# uart_adm3222.net
KiCad netlist of a schematic drawn in Altium Designer
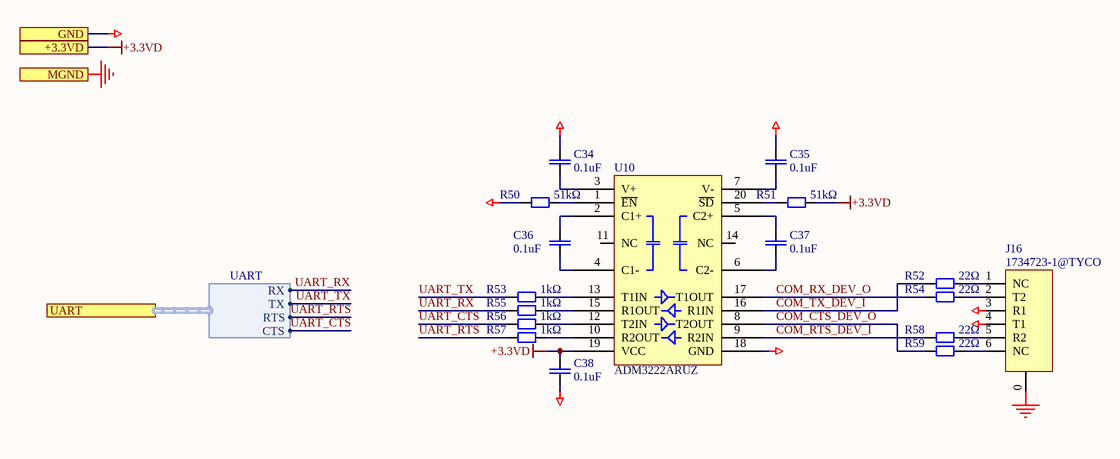
[diagram p0: uart_adm3222.SchDoc]

(export (version "E")
  (design (tool "Eeschema 10.0.6"))
  (components
    (comp (ref "C34")
      (value "0.1uF")
      (footprint "CAPC2012N")
      (description "Generic ceramic SMD capacitor")
      (fields (field (name "MAINTAINER") "Evgeniy Kotov"))
      (libsource (lib "[Capacitors] Capacitors SMD") (part "CAPC"))
    )
    (comp (ref "C35")
      (value "0.1uF")
      (footprint "CAPC2012N")
      (description "Generic ceramic SMD capacitor")
      (fields (field (name "MAINTAINER") "Evgeniy Kotov"))
      (libsource (lib "[Capacitors] Capacitors SMD") (part "CAPC"))
    )
    (comp (ref "C36")
      (value "0.1uF")
      (footprint "CAPC2012N")
      (description "Generic ceramic SMD capacitor")
      (fields (field (name "MAINTAINER") "Evgeniy Kotov"))
      (libsource (lib "[Capacitors] Capacitors SMD") (part "CAPC"))
    )
    (comp (ref "C37")
      (value "0.1uF")
      (footprint "CAPC2012N")
      (description "Generic ceramic SMD capacitor")
      (fields (field (name "MAINTAINER") "Evgeniy Kotov"))
      (libsource (lib "[Capacitors] Capacitors SMD") (part "CAPC"))
    )
    (comp (ref "C38")
      (value "0.1uF")
      (footprint "CAPC2012N")
      (description "Generic ceramic SMD capacitor")
      (fields (field (name "MAINTAINER") "Evgeniy Kotov"))
      (libsource (lib "[Capacitors] Capacitors SMD") (part "CAPC"))
    )
    (comp (ref "J16")
      (value "1734723-1@TYCO")
      (footprint "RJ14")
      (libsource (lib "[Connectors] Miscellaneous") (part "RJ-14"))
    )
    (comp (ref "R50")
      (value "51kΩ")
      (footprint "RESC2012N")
      (description "Resistor, Generic, SMD")
      (fields (field (name "MAINTAINER") "Evgeniy Kotov"))
      (libsource (lib "[Resistors] Resistors SMD") (part "RESC"))
    )
    (comp (ref "R51")
      (value "51kΩ")
      (footprint "RESC2012N")
      (description "Resistor, Generic, SMD")
      (fields (field (name "MAINTAINER") "Evgeniy Kotov"))
      (libsource (lib "[Resistors] Resistors SMD") (part "RESC"))
    )
    (comp (ref "R52")
      (value "22Ω")
      (footprint "RESC1608N")
      (description "Resistor, Generic, SMD")
      (fields (field (name "MAINTAINER") "Evgeniy Kotov"))
      (libsource (lib "[Resistors] Resistors SMD") (part "RESC"))
    )
    (comp (ref "R53")
      (value "1kΩ")
      (footprint "RESC2012N")
      (description "Resistor, Generic, SMD")
      (fields (field (name "MAINTAINER") "Evgeniy Kotov"))
      (libsource (lib "[Resistors] Resistors SMD") (part "RESC"))
    )
    (comp (ref "R54")
      (value "22Ω")
      (footprint "RESC1608N")
      (description "Resistor, Generic, SMD")
      (fields (field (name "MAINTAINER") "Evgeniy Kotov"))
      (libsource (lib "[Resistors] Resistors SMD") (part "RESC"))
    )
    (comp (ref "R55")
      (value "1kΩ")
      (footprint "RESC2012N")
      (description "Resistor, Generic, SMD")
      (fields (field (name "MAINTAINER") "Evgeniy Kotov"))
      (libsource (lib "[Resistors] Resistors SMD") (part "RESC"))
    )
    (comp (ref "R56")
      (value "1kΩ")
      (footprint "RESC2012N")
      (description "Resistor, Generic, SMD")
      (fields (field (name "MAINTAINER") "Evgeniy Kotov"))
      (libsource (lib "[Resistors] Resistors SMD") (part "RESC"))
    )
    (comp (ref "R57")
      (value "1kΩ")
      (footprint "RESC2012N")
      (description "Resistor, Generic, SMD")
      (fields (field (name "MAINTAINER") "Evgeniy Kotov"))
      (libsource (lib "[Resistors] Resistors SMD") (part "RESC"))
    )
    (comp (ref "R58")
      (value "22Ω")
      (footprint "RESC1608N")
      (description "Resistor, Generic, SMD")
      (fields (field (name "MAINTAINER") "Evgeniy Kotov"))
      (libsource (lib "[Resistors] Resistors SMD") (part "RESC"))
    )
    (comp (ref "R59")
      (value "22Ω")
      (footprint "RESC1608N")
      (description "Resistor, Generic, SMD")
      (fields (field (name "MAINTAINER") "Evgeniy Kotov"))
      (libsource (lib "[Resistors] Resistors SMD") (part "RESC"))
    )
    (comp (ref "U10")
      (value "ADM3222ARUZ")
      (footprint "SOP65P640X110-20N")
      (description "RS232")
      (libsource (lib "[ICs And Semiconductors] Analog & Interface") (part "ADM3222ARU"))
    )
  )
  (nets
    (net (code "2") (name "+3.3VD") (class "Default")
      (node (ref "C38") (pin "2") (pintype "passive"))
      (node (ref "R51") (pin "2") (pintype "passive"))
      (node (ref "U10") (pin "19") (pinfunction "VCC_19") (pintype "passive"))
    )
    (net (code "3") (name "/COM_CTS_DEV_O") (class "Default")
      (node (ref "R59") (pin "1") (pintype "passive"))
      (node (ref "U10") (pin "8") (pinfunction "T2OUT_8") (pintype "passive"))
    )
    (net (code "4") (name "/COM_RTS_DEV_I") (class "Default")
      (node (ref "R58") (pin "1") (pintype "passive"))
      (node (ref "U10") (pin "9") (pinfunction "R2IN_9") (pintype "passive"))
    )
    (net (code "5") (name "/COM_RX_DEV_O") (class "Default")
      (node (ref "R54") (pin "1") (pintype "passive"))
      (node (ref "U10") (pin "17") (pinfunction "T1OUT_17") (pintype "passive"))
    )
    (net (code "6") (name "/COM_TX_DEV_I") (class "Default")
      (node (ref "R52") (pin "1") (pintype "passive"))
      (node (ref "U10") (pin "16") (pinfunction "R1IN_16") (pintype "passive"))
    )
    (net (code "7") (name "/UART_CTS") (class "Default") (node (ref "R56") (pin "1") (pintype "passive")))
    (net (code "8") (name "/UART_RTS") (class "Default") (node (ref "R57") (pin "1") (pintype "passive")))
    (net (code "9") (name "/UART_RX") (class "Default") (node (ref "R55") (pin "1") (pintype "passive")))
    (net (code "10") (name "/UART_TX") (class "Default") (node (ref "R53") (pin "1") (pintype "passive")))
    (net (code "12") (name "GND") (class "Default")
      (node (ref "C34") (pin "2") (pintype "passive"))
      (node (ref "C35") (pin "2") (pintype "passive"))
      (node (ref "C38") (pin "1") (pintype "passive"))
      (node (ref "J16") (pin "3") (pinfunction "R1_3") (pintype "passive"))
      (node (ref "J16") (pin "4") (pinfunction "T1_4") (pintype "passive"))
      (node (ref "R50") (pin "1") (pintype "passive"))
      (node (ref "U10") (pin "18") (pinfunction "GND_18") (pintype "passive"))
    )
    (net (code "13") (name "MGND") (class "Default") (node (ref "J16") (pin "0") (pintype "passive")))
    (net (code "14") (name "Net-(J16-NC-Pad1)") (class "Default")
      (node (ref "J16") (pin "1") (pinfunction "NC_1") (pintype "passive"))
      (node (ref "R52") (pin "2") (pintype "passive"))
    )
    (net (code "15") (name "Net-(J16-NC-Pad6)") (class "Default")
      (node (ref "J16") (pin "6") (pinfunction "NC_6") (pintype "passive"))
      (node (ref "R59") (pin "2") (pintype "passive"))
    )
    (net (code "16") (name "Net-(J16-R2)") (class "Default")
      (node (ref "J16") (pin "5") (pinfunction "R2_5") (pintype "passive"))
      (node (ref "R58") (pin "2") (pintype "passive"))
    )
    (net (code "17") (name "Net-(J16-T2)") (class "Default")
      (node (ref "J16") (pin "2") (pinfunction "T2_2") (pintype "passive"))
      (node (ref "R54") (pin "2") (pintype "passive"))
    )
    (net (code "18") (name "Net-(U10-C1+)") (class "Default")
      (node (ref "C36") (pin "2") (pintype "passive"))
      (node (ref "U10") (pin "2") (pinfunction "C1+_2") (pintype "passive"))
    )
    (net (code "19") (name "Net-(U10-C1-)") (class "Default")
      (node (ref "C36") (pin "1") (pintype "passive"))
      (node (ref "U10") (pin "4") (pinfunction "C1-_4") (pintype "passive"))
    )
    (net (code "20") (name "Net-(U10-C2+)") (class "Default")
      (node (ref "C37") (pin "2") (pintype "passive"))
      (node (ref "U10") (pin "5") (pinfunction "C2+_5") (pintype "passive"))
    )
    (net (code "21") (name "Net-(U10-C2-)") (class "Default")
      (node (ref "C37") (pin "1") (pintype "passive"))
      (node (ref "U10") (pin "6") (pinfunction "C2-_6") (pintype "passive"))
    )
    (net (code "22") (name "Net-(U10-R1OUT)") (class "Default")
      (node (ref "R55") (pin "2") (pintype "passive"))
      (node (ref "U10") (pin "15") (pinfunction "R1OUT_15") (pintype "passive"))
    )
    (net (code "23") (name "Net-(U10-R2OUT)") (class "Default")
      (node (ref "R57") (pin "2") (pintype "passive"))
      (node (ref "U10") (pin "10") (pinfunction "R2OUT_10") (pintype "passive"))
    )
    (net (code "24") (name "Net-(U10-T1IN)") (class "Default")
      (node (ref "R53") (pin "2") (pintype "passive"))
      (node (ref "U10") (pin "13") (pinfunction "T1IN_13") (pintype "passive"))
    )
    (net (code "25") (name "Net-(U10-T2IN)") (class "Default")
      (node (ref "R56") (pin "2") (pintype "passive"))
      (node (ref "U10") (pin "12") (pinfunction "T2IN_12") (pintype "passive"))
    )
    (net (code "26") (name "Net-(U10-V+)") (class "Default")
      (node (ref "C34") (pin "1") (pintype "passive"))
      (node (ref "U10") (pin "3") (pinfunction "V+_3") (pintype "passive"))
    )
    (net (code "27") (name "Net-(U10-V-)") (class "Default")
      (node (ref "C35") (pin "1") (pintype "passive"))
      (node (ref "U10") (pin "7") (pinfunction "V-_7") (pintype "passive"))
    )
    (net (code "28") (name "Net-(U10-~{EN})") (class "Default")
      (node (ref "R50") (pin "2") (pintype "passive"))
      (node (ref "U10") (pin "1") (pinfunction "~{EN}_1") (pintype "passive"))
    )
    (net (code "29") (name "Net-(U10-~{SD})") (class "Default")
      (node (ref "R51") (pin "1") (pintype "passive"))
      (node (ref "U10") (pin "20") (pinfunction "~{SD}_20") (pintype "passive"))
    )
    (net (code "30") (name "unconnected-(U10-NC-Pad11)") (class "Default")
      (node (ref "U10") (pin "11") (pinfunction "NC_11") (pintype "passive"))
    )
    (net (code "31") (name "unconnected-(U10-NC-Pad14)") (class "Default")
      (node (ref "U10") (pin "14") (pinfunction "NC_14") (pintype "passive"))
    )
  )
)
